# SPWM.net
KiCad netlist of a schematic drawn in Altium Designer
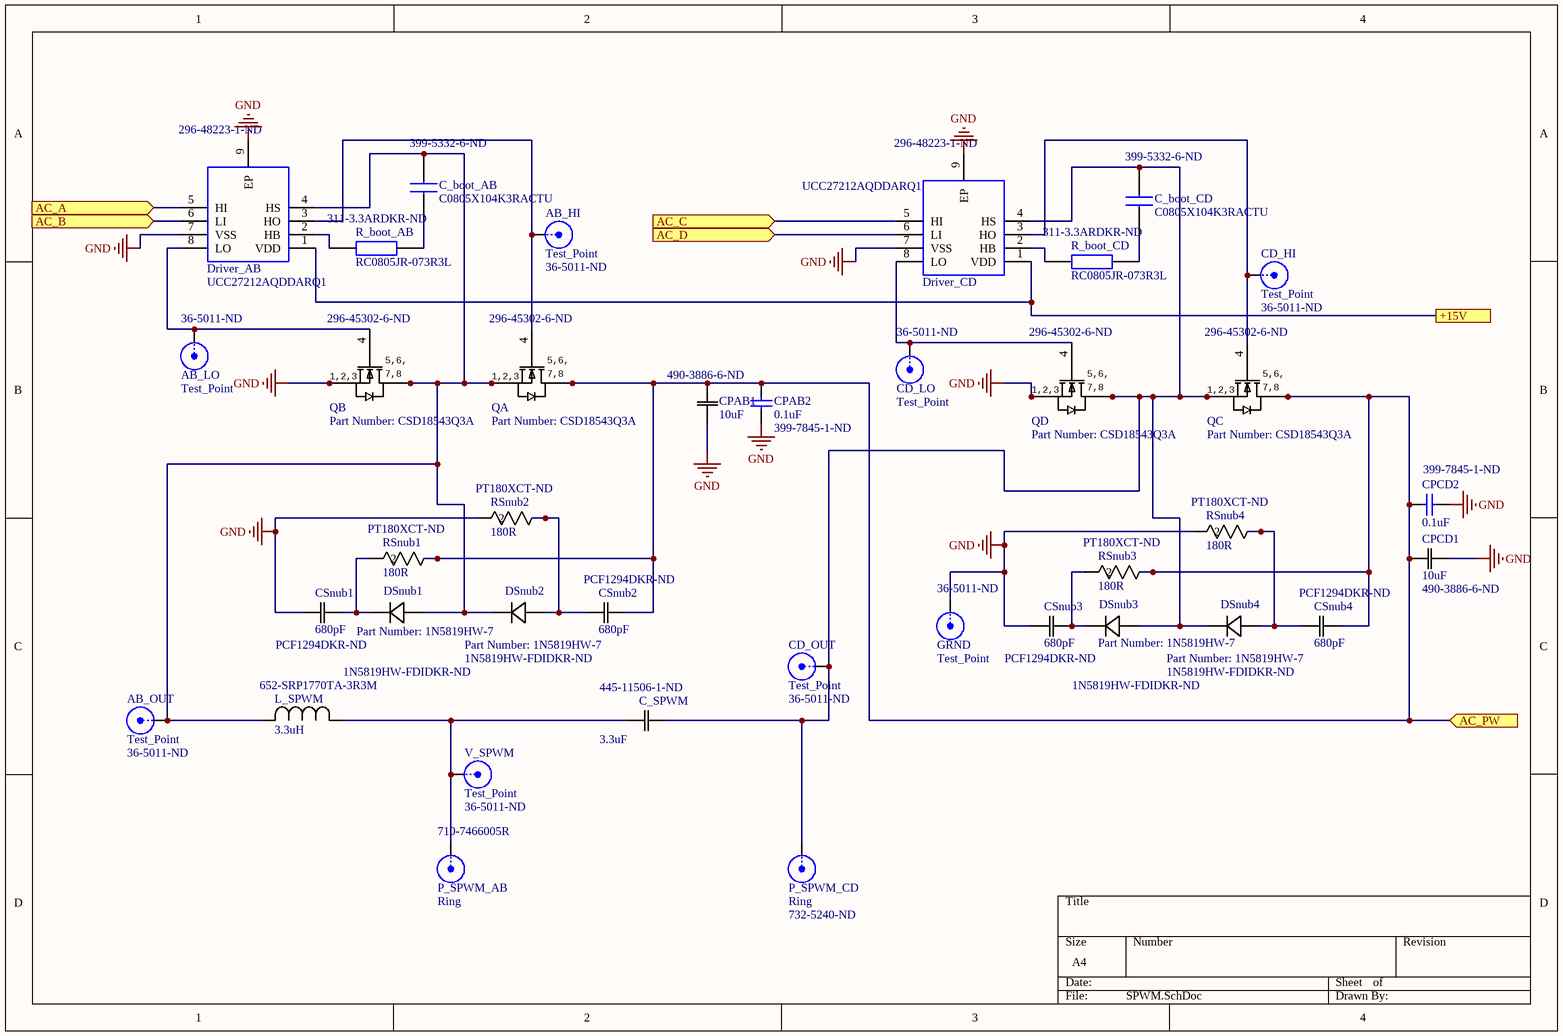
[diagram p0: SPWM.SchDoc]

(export (version "E")
  (design (tool "Eeschema 10.0.6"))
  (components
    (comp (ref "AB_HI")
      (value "Test_Point")
      (footprint "5011")
      (fields
        (field (name "SUPPLIER PART NUMBER 1") "36-5011-ND")
        (field (name "MANUFACTURER") "Keystone Electronics")
        (field (name "MANUFACTURER PART NUMBER") "5011")
      )
      (libsource (lib "Miscellaneous Connectors") (part "BNC"))
    )
    (comp (ref "AB_LO")
      (value "Test_Point")
      (footprint "5011")
      (fields
        (field (name "SUPPLIER PART NUMBER 1") "36-5011-ND")
        (field (name "MANUFACTURER") "Keystone Electronics")
        (field (name "MANUFACTURER PART NUMBER") "5011")
      )
      (libsource (lib "Miscellaneous Connectors") (part "BNC"))
    )
    (comp (ref "AB_OUT")
      (value "Test_Point")
      (footprint "5011")
      (fields
        (field (name "SUPPLIER PART NUMBER 1") "36-5011-ND")
        (field (name "MANUFACTURER") "Keystone Electronics")
        (field (name "MANUFACTURER PART NUMBER") "5011")
      )
      (libsource (lib "Miscellaneous Connectors") (part "BNC"))
    )
    (comp (ref "CD_HI")
      (value "Test_Point")
      (footprint "5011")
      (fields
        (field (name "SUPPLIER PART NUMBER 1") "36-5011-ND")
        (field (name "MANUFACTURER") "Keystone Electronics")
        (field (name "MANUFACTURER PART NUMBER") "5011")
      )
      (libsource (lib "Miscellaneous Connectors") (part "BNC"))
    )
    (comp (ref "CD_LO")
      (value "Test_Point")
      (footprint "5011")
      (fields
        (field (name "SUPPLIER PART NUMBER 1") "36-5011-ND")
        (field (name "MANUFACTURER") "Keystone Electronics")
        (field (name "MANUFACTURER PART NUMBER") "5011")
      )
      (libsource (lib "Miscellaneous Connectors") (part "BNC"))
    )
    (comp (ref "CD_OUT")
      (value "Test_Point")
      (footprint "5011")
      (fields
        (field (name "SUPPLIER PART NUMBER 1") "36-5011-ND")
        (field (name "MANUFACTURER") "Keystone Electronics")
        (field (name "MANUFACTURER PART NUMBER") "5011")
      )
      (libsource (lib "Miscellaneous Connectors") (part "BNC"))
    )
    (comp (ref "CPAB1")
      (value "10uF")
      (footprint "G-21")
      (description "No Description Available")
      (fields
        (field (name "MANUFACTURER_PART_NUMBER") "GRM21BR61C106KE15L")
        (field (name "SUPPLIER PART NUMBER 1") "490-3886-6-ND")
        (field (name "MANUFACTURER") "Murata")
        (field (name "COPYRIGHT") "Copyright (C) 2015 Accelerated Designs. All rights reserved")
      )
      (libsource (lib "GRM21BR61C106KE15L") (part "GRM21BR61C106KE1"))
    )
    (comp (ref "CPAB2")
      (value "0.1uF")
      (footprint "1608[0603]")
      (fields
        (field (name "SUPPLIER PART NUMBER 1") "399-7845-1-ND")
        (field (name "MANUFACTURER") "KEMET")
        (field (name "MANUFACTURER PART NUMBER") "C0603C104M5RACTU")
        (field (name "TOLERANCE") "20%")
      )
      (libsource (lib "Miscellaneous Devices") (part "Cap Semi"))
    )
    (comp (ref "CPCD1")
      (value "10uF")
      (footprint "G-21")
      (description "No Description Available")
      (fields
        (field (name "MANUFACTURER_PART_NUMBER") "GRM21BR61C106KE15L")
        (field (name "SUPPLIER PART NUMBER 1") "490-3886-6-ND")
        (field (name "MANUFACTURER") "Murata")
        (field (name "COPYRIGHT") "Copyright (C) 2015 Accelerated Designs. All rights reserved")
      )
      (libsource (lib "GRM21BR61C106KE15L") (part "GRM21BR61C106KE1"))
    )
    (comp (ref "CPCD2")
      (value "0.1uF")
      (footprint "1608[0603]")
      (fields
        (field (name "SUPPLIER PART NUMBER 1") "399-7845-1-ND")
        (field (name "MANUFACTURER") "KEMET")
        (field (name "MANUFACTURER PART NUMBER") "C0603C104M5RACTU")
        (field (name "TOLERANCE") "20%")
      )
      (libsource (lib "Miscellaneous Devices") (part "Cap Semi"))
    )
    (comp (ref "CSnub1")
      (value "680pF")
      (footprint "CAP_J1")
      (description "No Description Available")
      (fields
        (field (name "MANUFACTURER_PART_NUMBER") "ECHU1H681GX5")
        (field (name "SUPPLIER PART NUMBER 1") "PCF1294DKR-ND")
        (field (name "MANUFACTURER") "Panasonic")
        (field (name "COPYRIGHT") "Copyright (C) 2018 Accelerated Designs. All rights reserved")
      )
      (libsource (lib "ECHU1H681GX5") (part "ECHU1H681GX5"))
    )
    (comp (ref "CSnub2")
      (value "680pF")
      (footprint "CAP_J1")
      (description "No Description Available")
      (fields
        (field (name "MANUFACTURER_PART_NUMBER") "ECHU1H681GX5")
        (field (name "SUPPLIER PART NUMBER 1") "PCF1294DKR-ND")
        (field (name "MANUFACTURER") "Panasonic")
        (field (name "COPYRIGHT") "Copyright (C) 2018 Accelerated Designs. All rights reserved")
      )
      (libsource (lib "ECHU1H681GX5") (part "ECHU1H681GX5"))
    )
    (comp (ref "CSnub3")
      (value "680pF")
      (footprint "CAP_J1")
      (description "No Description Available")
      (fields
        (field (name "MANUFACTURER_PART_NUMBER") "ECHU1H681GX5")
        (field (name "SUPPLIER PART NUMBER 1") "PCF1294DKR-ND")
        (field (name "MANUFACTURER") "Panasonic")
        (field (name "COPYRIGHT") "Copyright (C) 2018 Accelerated Designs. All rights reserved")
      )
      (libsource (lib "ECHU1H681GX5") (part "ECHU1H681GX5"))
    )
    (comp (ref "CSnub4")
      (value "680pF")
      (footprint "CAP_J1")
      (description "No Description Available")
      (fields
        (field (name "MANUFACTURER_PART_NUMBER") "ECHU1H681GX5")
        (field (name "SUPPLIER PART NUMBER 1") "PCF1294DKR-ND")
        (field (name "MANUFACTURER") "Panasonic")
        (field (name "COPYRIGHT") "Copyright (C) 2018 Accelerated Designs. All rights reserved")
      )
      (libsource (lib "ECHU1H681GX5") (part "ECHU1H681GX5"))
    )
    (comp (ref "C_boot_AB")
      (value "C0805X104K3RACTU")
      (footprint "CAPC2012X98N")
      (description "Multilayer Ceramic Capacitors MLCC - SMD/SMT 25V 0.1uF 10%")
      (fields
        (field (name "SUPPLIER PART NUMBER 1") "399-5332-6-ND")
        (field (name "MANUFACTURER") "KEMET")
        (field (name "TOLERANCE") "10%")
      )
      (libsource (lib "C0805X104K3RACTU") (part "C0805X104K3RACTU"))
    )
    (comp (ref "C_boot_CD")
      (value "C0805X104K3RACTU")
      (footprint "CAPC2012X98N")
      (description "Multilayer Ceramic Capacitors MLCC - SMD/SMT 25V 0.1uF 10%")
      (fields
        (field (name "SUPPLIER PART NUMBER 1") "399-5332-6-ND")
        (field (name "MANUFACTURER") "KEMET")
        (field (name "TOLERANCE") "10%")
      )
      (libsource (lib "C0805X104K3RACTU") (part "C0805X104K3RACTU"))
    )
    (comp (ref "C_SPWM")
      (value "3.3uF")
      (footprint "CAP_2012")
      (description "No Description Available")
      (fields
        (field (name "MANUFACTURER_PART_NUMBER") "C2012JB1H335K125AB")
        (field (name "SUPPLIER PART NUMBER 1") "445-11506-1-ND")
        (field (name "MANUFACTURER") "TDK")
        (field (name "COPYRIGHT") "Copyright (C) 2018 Accelerated Designs. All rights reserved")
      )
      (libsource (lib "C2012JB1H335K125AB") (part "C2012JB1H335K125"))
    )
    (comp (ref "Driver_AB")
      (value "UCC27212AQDDARQ1")
      (footprint "SOIC127P600X170-9N")
      (description "Automotive, 120-V Boot, 4-A Peak, High-Frequency High-Side and Low-Side Driver")
      (fields
        (field (name "SUPPLIER PART NUMBER 1") "296-48223-1-ND")
        (field (name "MANUFACTURER") "Texas Instruments")
      )
      (libsource (lib "UCC27212AQDDARQ1") (part "UCC27212AQDDARQ1"))
    )
    (comp (ref "Driver_CD")
      (value "UCC27212AQDDARQ1")
      (footprint "SOIC127P600X170-9N")
      (description "Automotive, 120-V Boot, 4-A Peak, High-Frequency High-Side and Low-Side Driver")
      (fields
        (field (name "SUPPLIER PART NUMBER 1") "296-48223-1-ND")
        (field (name "MANUFACTURER") "Texas Instruments")
      )
      (libsource (lib "UCC27212AQDDARQ1") (part "UCC27212AQDDARQ1"))
    )
    (comp (ref "DSnub1")
      (value "Part Number: 1N5819HW-7")
      (footprint "SOD123")
      (description "No Description Available")
      (fields
        (field (name "MANUFACTURER_PART_NUMBER") "1N5819HW-7")
        (field (name "SUPPLIER PART NUMBER 1") "1N5819HW-FDIDKR-ND")
        (field (name "MANUFACTURER") "Diodes")
        (field (name "COPYRIGHT") "Copyright (C) 2018 Accelerated Designs. All rights reserved")
      )
      (libsource (lib "1N5819HW7") (part "1N5819HW-7"))
    )
    (comp (ref "DSnub2")
      (value "Part Number: 1N5819HW-7")
      (footprint "SOD123")
      (description "No Description Available")
      (fields
        (field (name "MANUFACTURER_PART_NUMBER") "1N5819HW-7")
        (field (name "SUPPLIER PART NUMBER 1") "1N5819HW-FDIDKR-ND")
        (field (name "MANUFACTURER") "Diodes")
        (field (name "COPYRIGHT") "Copyright (C) 2018 Accelerated Designs. All rights reserved")
      )
      (libsource (lib "1N5819HW7") (part "1N5819HW-7"))
    )
    (comp (ref "DSnub3")
      (value "Part Number: 1N5819HW-7")
      (footprint "SOD123")
      (description "No Description Available")
      (fields
        (field (name "MANUFACTURER_PART_NUMBER") "1N5819HW-7")
        (field (name "SUPPLIER PART NUMBER 1") "1N5819HW-FDIDKR-ND")
        (field (name "MANUFACTURER") "Diodes")
        (field (name "COPYRIGHT") "Copyright (C) 2018 Accelerated Designs. All rights reserved")
      )
      (libsource (lib "1N5819HW7") (part "1N5819HW-7"))
    )
    (comp (ref "DSnub4")
      (value "Part Number: 1N5819HW-7")
      (footprint "SOD123")
      (description "No Description Available")
      (fields
        (field (name "MANUFACTURER_PART_NUMBER") "1N5819HW-7")
        (field (name "SUPPLIER PART NUMBER 1") "1N5819HW-FDIDKR-ND")
        (field (name "MANUFACTURER") "Diodes")
        (field (name "COPYRIGHT") "Copyright (C) 2018 Accelerated Designs. All rights reserved")
      )
      (libsource (lib "1N5819HW7") (part "1N5819HW-7"))
    )
    (comp (ref "GRND")
      (value "Test_Point")
      (footprint "5011")
      (fields
        (field (name "SUPPLIER PART NUMBER 1") "36-5011-ND")
        (field (name "MANUFACTURER") "Keystone Electronics")
        (field (name "MANUFACTURER PART NUMBER") "5011")
      )
      (libsource (lib "Miscellaneous Connectors") (part "BNC"))
    )
    (comp (ref "L_SPWM")
      (value "3.3uH")
      (footprint "IND_TA-101M")
      (description "No Description Available")
      (fields
        (field (name "SUPPLIER PART NUMBER 1") "652-SRP1770TA-3R3M")
        (field (name "MANUFACTURER") "Bourns")
        (field (name "MANUFACTURER PART NUMBER") "SRP1770TA-3R3M")
      )
      (libsource (lib "SRP1770C-3R3M") (part "SRP1770TA-101M"))
    )
    (comp (ref "P_SPWM_AB")
      (value "Ring")
      (footprint "7466005R")
      (description "Ring Connector")
      (fields
        (field (name "SUPPLIER PART NUMBER 1") "710-7466005R")
        (field (name "MANUFACTURER") "Wurth Electronics")
        (field (name "MANUFACTURER PART NUMBER") "7466005R")
      )
      (libsource (lib "Miscellaneous Connectors") (part "BNC"))
    )
    (comp (ref "P_SPWM_CD")
      (value "Ring")
      (footprint "7466005R")
      (description "Ring Connector")
      (fields
        (field (name "SUPPLIER PART NUMBER 1") "732-5240-ND")
        (field (name "MANUFACTURER") "Wurth Electronics")
        (field (name "MANUFACTURER PART NUMBER") "7466003")
        (field (name "PUBLISHER") "Altium Limited")
      )
      (libsource (lib "Miscellaneous Connectors") (part "BNC"))
    )
    (comp (ref "QA")
      (value "Part Number: CSD18543Q3A")
      (footprint "DNH0008AT")
      (description "No Description Available")
      (fields
        (field (name "MANUFACTURER_PART_NUMBER") "CSD18543Q3A")
        (field (name "SUPPLIER PART NUMBER 1") "296-45302-6-ND")
        (field (name "COPYRIGHT") "Copyright (C) 2018 Accelerated Designs. All rights reserved")
      )
      (libsource (lib "CSD18543Q3A") (part "CSD18543Q3A"))
    )
    (comp (ref "QB")
      (value "Part Number: CSD18543Q3A")
      (footprint "DNH0008AT")
      (description "No Description Available")
      (fields
        (field (name "MANUFACTURER_PART_NUMBER") "CSD18543Q3A")
        (field (name "SUPPLIER PART NUMBER 1") "296-45302-6-ND")
        (field (name "COPYRIGHT") "Copyright (C) 2018 Accelerated Designs. All rights reserved")
      )
      (libsource (lib "CSD18543Q3A") (part "CSD18543Q3A"))
    )
    (comp (ref "QC")
      (value "Part Number: CSD18543Q3A")
      (footprint "DNH0008AT")
      (description "No Description Available")
      (fields
        (field (name "MANUFACTURER_PART_NUMBER") "CSD18543Q3A")
        (field (name "SUPPLIER PART NUMBER 1") "296-45302-6-ND")
        (field (name "COPYRIGHT") "Copyright (C) 2018 Accelerated Designs. All rights reserved")
      )
      (libsource (lib "CSD18543Q3A") (part "CSD18543Q3A"))
    )
    (comp (ref "QD")
      (value "Part Number: CSD18543Q3A")
      (footprint "DNH0008AT")
      (description "No Description Available")
      (fields
        (field (name "MANUFACTURER_PART_NUMBER") "CSD18543Q3A")
        (field (name "SUPPLIER PART NUMBER 1") "296-45302-6-ND")
        (field (name "COPYRIGHT") "Copyright (C) 2018 Accelerated Designs. All rights reserved")
      )
      (libsource (lib "CSD18543Q3A") (part "CSD18543Q3A"))
    )
    (comp (ref "RSnub1")
      (value "180R")
      (footprint "RC2512N")
      (description "No Description Available")
      (fields
        (field (name "MANUFACTURER_PART_NUMBER") "ERJ-1TYJ181U")
        (field (name "SUPPLIER PART NUMBER 1") "PT180XCT-ND")
        (field (name "MANUFACTURER") "Panasonic")
        (field (name "COPYRIGHT") "Copyright (C) 2018 Accelerated Designs. All rights reserved")
      )
      (libsource (lib "PT180XCT-ND") (part "ERJ-1TYJ181U"))
    )
    (comp (ref "RSnub2")
      (value "180R")
      (footprint "RC2512N")
      (description "No Description Available")
      (fields
        (field (name "MANUFACTURER_PART_NUMBER") "ERJ-1TYJ181U")
        (field (name "SUPPLIER PART NUMBER 1") "PT180XCT-ND")
        (field (name "MANUFACTURER") "Panasonic")
        (field (name "COPYRIGHT") "Copyright (C) 2018 Accelerated Designs. All rights reserved")
      )
      (libsource (lib "PT180XCT-ND") (part "ERJ-1TYJ181U"))
    )
    (comp (ref "RSnub3")
      (value "180R")
      (footprint "RC2512N")
      (description "No Description Available")
      (fields
        (field (name "MANUFACTURER_PART_NUMBER") "ERJ-1TYJ181U")
        (field (name "SUPPLIER PART NUMBER 1") "PT180XCT-ND")
        (field (name "MANUFACTURER") "Panasonic")
        (field (name "COPYRIGHT") "Copyright (C) 2018 Accelerated Designs. All rights reserved")
      )
      (libsource (lib "PT180XCT-ND") (part "ERJ-1TYJ181U"))
    )
    (comp (ref "RSnub4")
      (value "180R")
      (footprint "RC2512N")
      (description "No Description Available")
      (fields
        (field (name "MANUFACTURER_PART_NUMBER") "ERJ-1TYJ181U")
        (field (name "SUPPLIER PART NUMBER 1") "PT180XCT-ND")
        (field (name "MANUFACTURER") "Panasonic")
        (field (name "COPYRIGHT") "Copyright (C) 2018 Accelerated Designs. All rights reserved")
      )
      (libsource (lib "PT180XCT-ND") (part "ERJ-1TYJ181U"))
    )
    (comp (ref "R_boot_AB")
      (value "RC0805JR-073R3L")
      (footprint "RESC2012X60N")
      (description "Thick Film Resistors - SMD 3.3 OHM 5%")
      (fields
        (field (name "SUPPLIER PART NUMBER 1") "311-3.3ARDKR-ND")
        (field (name "MANUFACTURER") "Yageo")
        (field (name "TOLERANCE") "5%")
      )
      (libsource (lib "RC0805JR-073R3L") (part "RC0805JR-073R3L"))
    )
    (comp (ref "R_boot_CD")
      (value "RC0805JR-073R3L")
      (footprint "RESC2012X60N")
      (description "Thick Film Resistors - SMD 3.3 OHM 5%")
      (fields
        (field (name "SUPPLIER PART NUMBER 1") "311-3.3ARDKR-ND")
        (field (name "MANUFACTURER") "Yageo")
        (field (name "TOLERANCE") "5%")
      )
      (libsource (lib "RC0805JR-073R3L") (part "RC0805JR-073R3L"))
    )
    (comp (ref "V_SPWM")
      (value "Test_Point")
      (footprint "5011")
      (fields
        (field (name "SUPPLIER PART NUMBER 1") "36-5011-ND")
        (field (name "MANUFACTURER") "Keystone Electronics")
        (field (name "MANUFACTURER PART NUMBER") "5011")
      )
      (libsource (lib "Miscellaneous Connectors") (part "BNC"))
    )
  )
  (nets
    (net (code "1") (name "/+15V") (class "Default")
      (node (ref "Driver_AB") (pin "1") (pinfunction "VDD_1") (pintype "passive"))
      (node (ref "Driver_CD") (pin "1") (pinfunction "VDD_1") (pintype "passive"))
    )
    (net (code "2") (name "/AC_A") (class "Default")
      (node (ref "Driver_AB") (pin "5") (pinfunction "HI_5") (pintype "passive"))
    )
    (net (code "3") (name "/AC_B") (class "Default")
      (node (ref "Driver_AB") (pin "6") (pinfunction "LI_6") (pintype "passive"))
    )
    (net (code "4") (name "/AC_C") (class "Default")
      (node (ref "Driver_CD") (pin "5") (pinfunction "HI_5") (pintype "passive"))
    )
    (net (code "5") (name "/AC_D") (class "Default")
      (node (ref "Driver_CD") (pin "6") (pinfunction "LI_6") (pintype "passive"))
    )
    (net (code "6") (name "/AC_PW") (class "Default")
      (node (ref "CPAB1") (pin "2") (pinfunction "2_2") (pintype "passive"))
      (node (ref "CPAB2") (pin "2") (pinfunction "2_2") (pintype "passive"))
      (node (ref "CPCD1") (pin "2") (pinfunction "2_2") (pintype "passive"))
      (node (ref "CPCD2") (pin "2") (pinfunction "2_2") (pintype "passive"))
      (node (ref "CSnub2") (pin "2") (pinfunction "2_2") (pintype "passive"))
      (node (ref "CSnub4") (pin "2") (pinfunction "2_2") (pintype "passive"))
      (node (ref "QA") (pin "5") (pinfunction "D_5") (pintype "passive"))
      (node (ref "QA") (pin "6") (pinfunction "D_6") (pintype "passive"))
      (node (ref "QA") (pin "7") (pinfunction "D_7") (pintype "passive"))
      (node (ref "QA") (pin "8") (pinfunction "D_8") (pintype "passive"))
      (node (ref "QA") (pin "9") (pinfunction "D_9") (pintype "passive"))
      (node (ref "QC") (pin "5") (pinfunction "D_5") (pintype "passive"))
      (node (ref "QC") (pin "6") (pinfunction "D_6") (pintype "passive"))
      (node (ref "QC") (pin "7") (pinfunction "D_7") (pintype "passive"))
      (node (ref "QC") (pin "8") (pinfunction "D_8") (pintype "passive"))
      (node (ref "QC") (pin "9") (pinfunction "D_9") (pintype "passive"))
      (node (ref "RSnub1") (pin "1") (pinfunction "1_1") (pintype "passive"))
      (node (ref "RSnub3") (pin "1") (pinfunction "1_1") (pintype "passive"))
    )
    (net (code "7") (name "GND") (class "Default")
      (node (ref "CPAB1") (pin "1") (pinfunction "1_1") (pintype "passive"))
      (node (ref "CPAB2") (pin "1") (pinfunction "1_1") (pintype "passive"))
      (node (ref "CPCD1") (pin "1") (pinfunction "1_1") (pintype "passive"))
      (node (ref "CPCD2") (pin "1") (pinfunction "1_1") (pintype "passive"))
      (node (ref "CSnub1") (pin "1") (pinfunction "1_1") (pintype "passive"))
      (node (ref "CSnub3") (pin "1") (pinfunction "1_1") (pintype "passive"))
      (node (ref "Driver_AB") (pin "7") (pinfunction "VSS_7") (pintype "passive"))
      (node (ref "Driver_AB") (pin "9") (pinfunction "EP_9") (pintype "passive"))
      (node (ref "Driver_CD") (pin "7") (pinfunction "VSS_7") (pintype "passive"))
      (node (ref "Driver_CD") (pin "9") (pinfunction "EP_9") (pintype "passive"))
      (node (ref "GRND") (pin "1") (pinfunction "X_1") (pintype "passive"))
      (node (ref "QB") (pin "1") (pinfunction "S_1") (pintype "passive"))
      (node (ref "QB") (pin "2") (pinfunction "S_2") (pintype "passive"))
      (node (ref "QB") (pin "3") (pinfunction "S_3") (pintype "passive"))
      (node (ref "QD") (pin "1") (pinfunction "S_1") (pintype "passive"))
      (node (ref "QD") (pin "2") (pinfunction "S_2") (pintype "passive"))
      (node (ref "QD") (pin "3") (pinfunction "S_3") (pintype "passive"))
      (node (ref "RSnub2") (pin "2") (pinfunction "2_2") (pintype "passive"))
      (node (ref "RSnub4") (pin "2") (pinfunction "2_2") (pintype "passive"))
    )
    (net (code "8") (name "Net-(AB_HI-X)") (class "Default")
      (node (ref "AB_HI") (pin "1") (pinfunction "X_1") (pintype "passive"))
      (node (ref "Driver_AB") (pin "3") (pinfunction "HO_3") (pintype "passive"))
      (node (ref "QA") (pin "4") (pinfunction "G_4") (pintype "passive"))
    )
    (net (code "9") (name "Net-(AB_LO-X)") (class "Default")
      (node (ref "AB_LO") (pin "1") (pinfunction "X_1") (pintype "passive"))
      (node (ref "Driver_AB") (pin "8") (pinfunction "LO_8") (pintype "passive"))
      (node (ref "QB") (pin "4") (pinfunction "G_4") (pintype "passive"))
    )
    (net (code "10") (name "Net-(AB_OUT-X)") (class "Default")
      (node (ref "AB_OUT") (pin "1") (pinfunction "X_1") (pintype "passive"))
      (node (ref "C_boot_AB") (pin "2") (pinfunction "2_2") (pintype "passive"))
      (node (ref "DSnub1") (pin "2") (pinfunction "2_2") (pintype "passive"))
      (node (ref "DSnub2") (pin "1") (pinfunction "1_1") (pintype "passive"))
      (node (ref "Driver_AB") (pin "4") (pinfunction "HS_4") (pintype "passive"))
      (node (ref "L_SPWM") (pin "2") (pinfunction "2_2") (pintype "passive"))
      (node (ref "QA") (pin "1") (pinfunction "S_1") (pintype "passive"))
      (node (ref "QA") (pin "2") (pinfunction "S_2") (pintype "passive"))
      (node (ref "QA") (pin "3") (pinfunction "S_3") (pintype "passive"))
      (node (ref "QB") (pin "5") (pinfunction "D_5") (pintype "passive"))
      (node (ref "QB") (pin "6") (pinfunction "D_6") (pintype "passive"))
      (node (ref "QB") (pin "7") (pinfunction "D_7") (pintype "passive"))
      (node (ref "QB") (pin "8") (pinfunction "D_8") (pintype "passive"))
      (node (ref "QB") (pin "9") (pinfunction "D_9") (pintype "passive"))
    )
    (net (code "11") (name "Net-(CD_HI-X)") (class "Default")
      (node (ref "CD_HI") (pin "1") (pinfunction "X_1") (pintype "passive"))
      (node (ref "Driver_CD") (pin "3") (pinfunction "HO_3") (pintype "passive"))
      (node (ref "QC") (pin "4") (pinfunction "G_4") (pintype "passive"))
    )
    (net (code "12") (name "Net-(CD_LO-X)") (class "Default")
      (node (ref "CD_LO") (pin "1") (pinfunction "X_1") (pintype "passive"))
      (node (ref "Driver_CD") (pin "8") (pinfunction "LO_8") (pintype "passive"))
      (node (ref "QD") (pin "4") (pinfunction "G_4") (pintype "passive"))
    )
    (net (code "13") (name "Net-(CD_OUT-X)") (class "Default")
      (node (ref "CD_OUT") (pin "1") (pinfunction "X_1") (pintype "passive"))
      (node (ref "C_SPWM") (pin "2") (pinfunction "2_2") (pintype "passive"))
      (node (ref "C_boot_CD") (pin "2") (pinfunction "2_2") (pintype "passive"))
      (node (ref "DSnub3") (pin "2") (pinfunction "2_2") (pintype "passive"))
      (node (ref "DSnub4") (pin "1") (pinfunction "1_1") (pintype "passive"))
      (node (ref "Driver_CD") (pin "4") (pinfunction "HS_4") (pintype "passive"))
      (node (ref "P_SPWM_CD") (pin "1") (pinfunction "X_1") (pintype "passive"))
      (node (ref "QC") (pin "1") (pinfunction "S_1") (pintype "passive"))
      (node (ref "QC") (pin "2") (pinfunction "S_2") (pintype "passive"))
      (node (ref "QC") (pin "3") (pinfunction "S_3") (pintype "passive"))
      (node (ref "QD") (pin "5") (pinfunction "D_5") (pintype "passive"))
      (node (ref "QD") (pin "6") (pinfunction "D_6") (pintype "passive"))
      (node (ref "QD") (pin "7") (pinfunction "D_7") (pintype "passive"))
      (node (ref "QD") (pin "8") (pinfunction "D_8") (pintype "passive"))
      (node (ref "QD") (pin "9") (pinfunction "D_9") (pintype "passive"))
    )
    (net (code "14") (name "Net-(CSnub1-Pad2)") (class "Default")
      (node (ref "CSnub1") (pin "2") (pinfunction "2_2") (pintype "passive"))
      (node (ref "DSnub1") (pin "1") (pinfunction "1_1") (pintype "passive"))
      (node (ref "RSnub1") (pin "2") (pinfunction "2_2") (pintype "passive"))
    )
    (net (code "15") (name "Net-(CSnub2-Pad1)") (class "Default")
      (node (ref "CSnub2") (pin "1") (pinfunction "1_1") (pintype "passive"))
      (node (ref "DSnub2") (pin "2") (pinfunction "2_2") (pintype "passive"))
      (node (ref "RSnub2") (pin "1") (pinfunction "1_1") (pintype "passive"))
    )
    (net (code "16") (name "Net-(CSnub3-Pad2)") (class "Default")
      (node (ref "CSnub3") (pin "2") (pinfunction "2_2") (pintype "passive"))
      (node (ref "DSnub3") (pin "1") (pinfunction "1_1") (pintype "passive"))
      (node (ref "RSnub3") (pin "2") (pinfunction "2_2") (pintype "passive"))
    )
    (net (code "17") (name "Net-(CSnub4-Pad1)") (class "Default")
      (node (ref "CSnub4") (pin "1") (pinfunction "1_1") (pintype "passive"))
      (node (ref "DSnub4") (pin "2") (pinfunction "2_2") (pintype "passive"))
      (node (ref "RSnub4") (pin "1") (pinfunction "1_1") (pintype "passive"))
    )
    (net (code "18") (name "Net-(C_boot_AB-Pad1)") (class "Default")
      (node (ref "C_boot_AB") (pin "1") (pinfunction "1_1") (pintype "passive"))
      (node (ref "R_boot_AB") (pin "2") (pinfunction "2_2") (pintype "passive"))
    )
    (net (code "19") (name "Net-(C_boot_CD-Pad1)") (class "Default")
      (node (ref "C_boot_CD") (pin "1") (pinfunction "1_1") (pintype "passive"))
      (node (ref "R_boot_CD") (pin "2") (pinfunction "2_2") (pintype "passive"))
    )
    (net (code "20") (name "Net-(Driver_AB-HB)") (class "Default")
      (node (ref "Driver_AB") (pin "2") (pinfunction "HB_2") (pintype "passive"))
      (node (ref "R_boot_AB") (pin "1") (pinfunction "1_1") (pintype "passive"))
    )
    (net (code "21") (name "Net-(Driver_CD-HB)") (class "Default")
      (node (ref "Driver_CD") (pin "2") (pinfunction "HB_2") (pintype "passive"))
      (node (ref "R_boot_CD") (pin "1") (pinfunction "1_1") (pintype "passive"))
    )
    (net (code "22") (name "Net-(P_SPWM_AB-X)") (class "Default")
      (node (ref "C_SPWM") (pin "1") (pinfunction "1_1") (pintype "passive"))
      (node (ref "L_SPWM") (pin "1") (pinfunction "1_1") (pintype "passive"))
      (node (ref "P_SPWM_AB") (pin "1") (pinfunction "X_1") (pintype "passive"))
      (node (ref "V_SPWM") (pin "1") (pinfunction "X_1") (pintype "passive"))
    )
  )
)
